# TinySparkShield.net
KiCad netlist of a schematic drawn in EAGLE
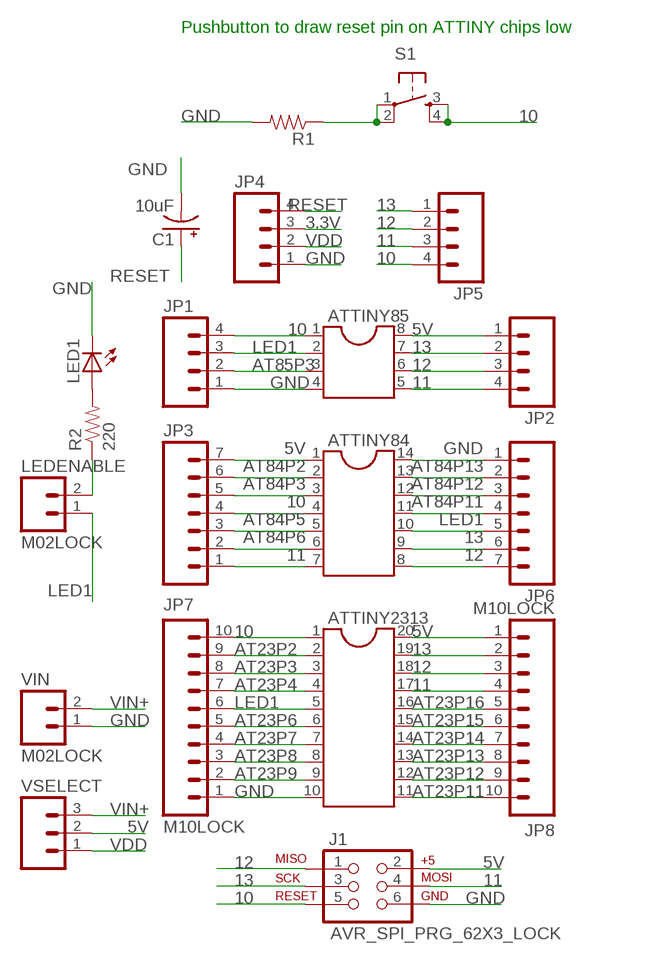
[diagram p0: schematic, sheet 1]

(export (version "E")
  (design (tool "Eeschema 10.0.6"))
  (components
    (comp (ref "ATTINY84")
      (value "DIL14")
      (footprint "eagle-import:DIL14")
      (libsource (lib "eagle-import") (part "DIL14"))
    )
    (comp (ref "ATTINY85")
      (value "DIL8")
      (footprint "eagle-import:DIL08")
      (libsource (lib "eagle-import") (part "DIL8"))
    )
    (comp (ref "ATTINY2313")
      (value "DIL20")
      (footprint "eagle-import:DIL20")
      (libsource (lib "eagle-import") (part "DIL20"))
    )
    (comp (ref "C1")
      (value "10uF")
      (footprint "eagle-import:CPOL-RADIAL-100UF-25V")
      (libsource (lib "eagle-import") (part "CAP_POLPTH1"))
    )
    (comp (ref "J1")
      (value "AVR_SPI_PRG_62X3_LOCK")
      (footprint "eagle-import:2X3_LOCK")
      (libsource (lib "eagle-import") (part "AVR_SPI_PRG_62X3_LOCK"))
    )
    (comp (ref "JP1")
      (value "M04LOCK")
      (footprint "eagle-import:1X04_LOCK")
      (libsource (lib "eagle-import") (part "M04LOCK"))
    )
    (comp (ref "JP2")
      (value "M04LOCK")
      (footprint "eagle-import:1X04_LOCK")
      (libsource (lib "eagle-import") (part "M04LOCK"))
    )
    (comp (ref "JP3")
      (value "M07LOCK")
      (footprint "eagle-import:1X07_LOCK")
      (libsource (lib "eagle-import") (part "M07LOCK"))
    )
    (comp (ref "JP4")
      (value "M04LOCK")
      (footprint "eagle-import:1X04_LOCK")
      (libsource (lib "eagle-import") (part "M04LOCK"))
    )
    (comp (ref "JP5")
      (value "M04LOCK")
      (footprint "eagle-import:1X04_LOCK")
      (libsource (lib "eagle-import") (part "M04LOCK"))
    )
    (comp (ref "JP6")
      (value "M07LOCK")
      (footprint "eagle-import:1X07_LOCK")
      (libsource (lib "eagle-import") (part "M07LOCK"))
    )
    (comp (ref "JP7")
      (value "M10LOCK")
      (footprint "eagle-import:1X10_LOCK")
      (libsource (lib "eagle-import") (part "M10LOCK"))
    )
    (comp (ref "JP8")
      (value "M10LOCK")
      (footprint "eagle-import:1X10_LOCK")
      (libsource (lib "eagle-import") (part "M10LOCK"))
    )
    (comp (ref "LED1")
      (value "LED3MM")
      (footprint "eagle-import:LED3MM")
      (libsource (lib "eagle-import") (part "LED3MM"))
    )
    (comp (ref "LEDENABLE")
      (value "M02LOCK")
      (footprint "eagle-import:1X02_LOCK")
      (libsource (lib "eagle-import") (part "M02LOCK"))
    )
    (comp (ref "R1")
      (value "RESISTORAXIAL-0.3")
      (footprint "eagle-import:AXIAL-0.3")
      (libsource (lib "eagle-import") (part "RESISTORAXIAL-0.3"))
    )
    (comp (ref "R2")
      (value "220")
      (footprint "eagle-import:AXIAL-0.3")
      (libsource (lib "eagle-import") (part "RESISTORAXIAL-0.3"))
    )
    (comp (ref "S1")
      (value "TAC_SWITCHPTH")
      (footprint "eagle-import:TACTILE-PTH")
      (libsource (lib "eagle-import") (part "TAC_SWITCHPTH"))
    )
    (comp (ref "VIN")
      (value "M02LOCK")
      (footprint "eagle-import:1X02_LOCK")
      (libsource (lib "eagle-import") (part "M02LOCK"))
    )
    (comp (ref "VSELECT")
      (value "M03LOCK")
      (footprint "eagle-import:1X03_LOCK")
      (libsource (lib "eagle-import") (part "M03LOCK"))
    )
  )
  (nets
    (net (code "1") (name "/3.3V") (class "Default")
      (node (ref "JP4") (pin "3") (pinfunction "3_3") (pintype "passive"))
    )
    (net (code "2") (name "/5V") (class "Default")
      (node (ref "ATTINY2313") (pin "20") (pinfunction "20_20") (pintype "passive"))
      (node (ref "ATTINY84") (pin "1") (pinfunction "1_1") (pintype "passive"))
      (node (ref "ATTINY85") (pin "8") (pinfunction "8_8") (pintype "passive"))
      (node (ref "J1") (pin "2") (pinfunction "2_2") (pintype "passive"))
      (node (ref "JP2") (pin "1") (pinfunction "1_1") (pintype "passive"))
      (node (ref "JP3") (pin "7") (pinfunction "7_7") (pintype "passive"))
      (node (ref "JP8") (pin "1") (pinfunction "1_1") (pintype "passive"))
      (node (ref "VSELECT") (pin "2") (pinfunction "2_2") (pintype "passive"))
    )
    (net (code "3") (name "/10") (class "Default")
      (node (ref "ATTINY2313") (pin "1") (pinfunction "1_1") (pintype "passive"))
      (node (ref "ATTINY84") (pin "4") (pinfunction "4_4") (pintype "passive"))
      (node (ref "ATTINY85") (pin "1") (pinfunction "1_1") (pintype "passive"))
      (node (ref "J1") (pin "5") (pinfunction "5_5") (pintype "passive"))
      (node (ref "JP1") (pin "4") (pinfunction "4_4") (pintype "passive"))
      (node (ref "JP3") (pin "4") (pinfunction "4_4") (pintype "passive"))
      (node (ref "JP5") (pin "4") (pinfunction "4_4") (pintype "passive"))
      (node (ref "JP7") (pin "10") (pinfunction "10_10") (pintype "passive"))
      (node (ref "S1") (pin "3") (pinfunction "3_3") (pintype "passive"))
      (node (ref "S1") (pin "4") (pinfunction "4_4") (pintype "passive"))
    )
    (net (code "4") (name "/11") (class "Default")
      (node (ref "ATTINY2313") (pin "17") (pinfunction "17_17") (pintype "passive"))
      (node (ref "ATTINY84") (pin "7") (pinfunction "7_7") (pintype "passive"))
      (node (ref "ATTINY85") (pin "5") (pinfunction "5_5") (pintype "passive"))
      (node (ref "J1") (pin "4") (pinfunction "4_4") (pintype "passive"))
      (node (ref "JP2") (pin "4") (pinfunction "4_4") (pintype "passive"))
      (node (ref "JP3") (pin "1") (pinfunction "1_1") (pintype "passive"))
      (node (ref "JP5") (pin "3") (pinfunction "3_3") (pintype "passive"))
      (node (ref "JP8") (pin "4") (pinfunction "4_4") (pintype "passive"))
    )
    (net (code "5") (name "/12") (class "Default")
      (node (ref "ATTINY2313") (pin "18") (pinfunction "18_18") (pintype "passive"))
      (node (ref "ATTINY84") (pin "8") (pinfunction "8_8") (pintype "passive"))
      (node (ref "ATTINY85") (pin "6") (pinfunction "6_6") (pintype "passive"))
      (node (ref "J1") (pin "1") (pinfunction "1_1") (pintype "passive"))
      (node (ref "JP2") (pin "3") (pinfunction "3_3") (pintype "passive"))
      (node (ref "JP5") (pin "2") (pinfunction "2_2") (pintype "passive"))
      (node (ref "JP6") (pin "7") (pinfunction "7_7") (pintype "passive"))
      (node (ref "JP8") (pin "3") (pinfunction "3_3") (pintype "passive"))
    )
    (net (code "6") (name "/13") (class "Default")
      (node (ref "ATTINY2313") (pin "19") (pinfunction "19_19") (pintype "passive"))
      (node (ref "ATTINY84") (pin "9") (pinfunction "9_9") (pintype "passive"))
      (node (ref "ATTINY85") (pin "7") (pinfunction "7_7") (pintype "passive"))
      (node (ref "J1") (pin "3") (pinfunction "3_3") (pintype "passive"))
      (node (ref "JP2") (pin "2") (pinfunction "2_2") (pintype "passive"))
      (node (ref "JP5") (pin "1") (pinfunction "1_1") (pintype "passive"))
      (node (ref "JP6") (pin "6") (pinfunction "6_6") (pintype "passive"))
      (node (ref "JP8") (pin "2") (pinfunction "2_2") (pintype "passive"))
    )
    (net (code "7") (name "/AT23P2") (class "Default")
      (node (ref "ATTINY2313") (pin "2") (pinfunction "2_2") (pintype "passive"))
      (node (ref "JP7") (pin "9") (pinfunction "9_9") (pintype "passive"))
    )
    (net (code "8") (name "/AT23P3") (class "Default")
      (node (ref "ATTINY2313") (pin "3") (pinfunction "3_3") (pintype "passive"))
      (node (ref "JP7") (pin "8") (pinfunction "8_8") (pintype "passive"))
    )
    (net (code "9") (name "/AT23P4") (class "Default")
      (node (ref "ATTINY2313") (pin "4") (pinfunction "4_4") (pintype "passive"))
      (node (ref "JP7") (pin "7") (pinfunction "7_7") (pintype "passive"))
    )
    (net (code "10") (name "/AT23P6") (class "Default")
      (node (ref "ATTINY2313") (pin "6") (pinfunction "6_6") (pintype "passive"))
      (node (ref "JP7") (pin "5") (pinfunction "5_5") (pintype "passive"))
    )
    (net (code "11") (name "/AT23P7") (class "Default")
      (node (ref "ATTINY2313") (pin "7") (pinfunction "7_7") (pintype "passive"))
      (node (ref "JP7") (pin "4") (pinfunction "4_4") (pintype "passive"))
    )
    (net (code "12") (name "/AT23P8") (class "Default")
      (node (ref "ATTINY2313") (pin "8") (pinfunction "8_8") (pintype "passive"))
      (node (ref "JP7") (pin "3") (pinfunction "3_3") (pintype "passive"))
    )
    (net (code "13") (name "/AT23P9") (class "Default")
      (node (ref "ATTINY2313") (pin "9") (pinfunction "9_9") (pintype "passive"))
      (node (ref "JP7") (pin "2") (pinfunction "2_2") (pintype "passive"))
    )
    (net (code "14") (name "/AT23P11") (class "Default")
      (node (ref "ATTINY2313") (pin "11") (pinfunction "11_11") (pintype "passive"))
      (node (ref "JP8") (pin "10") (pinfunction "10_10") (pintype "passive"))
    )
    (net (code "15") (name "/AT23P12") (class "Default")
      (node (ref "ATTINY2313") (pin "12") (pinfunction "12_12") (pintype "passive"))
      (node (ref "JP8") (pin "9") (pinfunction "9_9") (pintype "passive"))
    )
    (net (code "16") (name "/AT23P13") (class "Default")
      (node (ref "ATTINY2313") (pin "13") (pinfunction "13_13") (pintype "passive"))
      (node (ref "JP8") (pin "8") (pinfunction "8_8") (pintype "passive"))
    )
    (net (code "17") (name "/AT23P14") (class "Default")
      (node (ref "ATTINY2313") (pin "14") (pinfunction "14_14") (pintype "passive"))
      (node (ref "JP8") (pin "7") (pinfunction "7_7") (pintype "passive"))
    )
    (net (code "18") (name "/AT23P15") (class "Default")
      (node (ref "ATTINY2313") (pin "15") (pinfunction "15_15") (pintype "passive"))
      (node (ref "JP8") (pin "6") (pinfunction "6_6") (pintype "passive"))
    )
    (net (code "19") (name "/AT23P16") (class "Default")
      (node (ref "ATTINY2313") (pin "16") (pinfunction "16_16") (pintype "passive"))
      (node (ref "JP8") (pin "5") (pinfunction "5_5") (pintype "passive"))
    )
    (net (code "20") (name "/AT84P2") (class "Default")
      (node (ref "ATTINY84") (pin "2") (pinfunction "2_2") (pintype "passive"))
      (node (ref "JP3") (pin "6") (pinfunction "6_6") (pintype "passive"))
    )
    (net (code "21") (name "/AT84P3") (class "Default")
      (node (ref "ATTINY84") (pin "3") (pinfunction "3_3") (pintype "passive"))
      (node (ref "JP3") (pin "5") (pinfunction "5_5") (pintype "passive"))
    )
    (net (code "22") (name "/AT84P5") (class "Default")
      (node (ref "ATTINY84") (pin "5") (pinfunction "5_5") (pintype "passive"))
      (node (ref "JP3") (pin "3") (pinfunction "3_3") (pintype "passive"))
    )
    (net (code "23") (name "/AT84P6") (class "Default")
      (node (ref "ATTINY84") (pin "6") (pinfunction "6_6") (pintype "passive"))
      (node (ref "JP3") (pin "2") (pinfunction "2_2") (pintype "passive"))
    )
    (net (code "24") (name "/AT84P11") (class "Default")
      (node (ref "ATTINY84") (pin "11") (pinfunction "11_11") (pintype "passive"))
      (node (ref "JP6") (pin "4") (pinfunction "4_4") (pintype "passive"))
    )
    (net (code "25") (name "/AT84P12") (class "Default")
      (node (ref "ATTINY84") (pin "12") (pinfunction "12_12") (pintype "passive"))
      (node (ref "JP6") (pin "3") (pinfunction "3_3") (pintype "passive"))
    )
    (net (code "26") (name "/AT84P13") (class "Default")
      (node (ref "ATTINY84") (pin "13") (pinfunction "13_13") (pintype "passive"))
      (node (ref "JP6") (pin "2") (pinfunction "2_2") (pintype "passive"))
    )
    (net (code "27") (name "/AT85P3") (class "Default")
      (node (ref "ATTINY85") (pin "3") (pinfunction "3_3") (pintype "passive"))
      (node (ref "JP1") (pin "2") (pinfunction "2_2") (pintype "passive"))
    )
    (net (code "28") (name "/GND") (class "Default")
      (node (ref "ATTINY2313") (pin "10") (pinfunction "10_10") (pintype "passive"))
      (node (ref "ATTINY84") (pin "14") (pinfunction "14_14") (pintype "passive"))
      (node (ref "ATTINY85") (pin "4") (pinfunction "4_4") (pintype "passive"))
      (node (ref "C1") (pin "2") (pinfunction "-_2") (pintype "passive"))
      (node (ref "J1") (pin "6") (pinfunction "6_6") (pintype "passive"))
      (node (ref "JP1") (pin "1") (pinfunction "1_1") (pintype "passive"))
      (node (ref "JP4") (pin "1") (pinfunction "1_1") (pintype "passive"))
      (node (ref "JP6") (pin "1") (pinfunction "1_1") (pintype "passive"))
      (node (ref "JP7") (pin "1") (pinfunction "1_1") (pintype "passive"))
      (node (ref "LED1") (pin "K") (pinfunction "C_K") (pintype "passive"))
      (node (ref "R1") (pin "P$2") (pinfunction "2_P$2") (pintype "passive"))
      (node (ref "VIN") (pin "1") (pinfunction "1_1") (pintype "passive"))
    )
    (net (code "29") (name "/LED1") (class "Default")
      (node (ref "ATTINY2313") (pin "5") (pinfunction "5_5") (pintype "passive"))
      (node (ref "ATTINY84") (pin "10") (pinfunction "10_10") (pintype "passive"))
      (node (ref "ATTINY85") (pin "2") (pinfunction "2_2") (pintype "passive"))
      (node (ref "JP1") (pin "3") (pinfunction "3_3") (pintype "passive"))
      (node (ref "JP6") (pin "5") (pinfunction "5_5") (pintype "passive"))
      (node (ref "JP7") (pin "6") (pinfunction "6_6") (pintype "passive"))
      (node (ref "LEDENABLE") (pin "1") (pinfunction "1_1") (pintype "passive"))
    )
    (net (code "30") (name "/RESET") (class "Default")
      (node (ref "C1") (pin "1") (pinfunction "+_1") (pintype "passive"))
      (node (ref "JP4") (pin "4") (pinfunction "4_4") (pintype "passive"))
    )
    (net (code "31") (name "/VDD") (class "Default")
      (node (ref "JP4") (pin "2") (pinfunction "2_2") (pintype "passive"))
      (node (ref "VSELECT") (pin "1") (pinfunction "1_1") (pintype "passive"))
    )
    (net (code "32") (name "/VIN+") (class "Default")
      (node (ref "VIN") (pin "2") (pinfunction "2_2") (pintype "passive"))
      (node (ref "VSELECT") (pin "3") (pinfunction "3_3") (pintype "passive"))
    )
    (net (code "33") (name "Net-(R1-1)") (class "Default")
      (node (ref "R1") (pin "P$1") (pinfunction "1_P$1") (pintype "passive"))
      (node (ref "S1") (pin "1") (pinfunction "1_1") (pintype "passive"))
      (node (ref "S1") (pin "2") (pinfunction "2_2") (pintype "passive"))
    )
    (net (code "34") (name "Net-(R2-1)") (class "Default")
      (node (ref "LEDENABLE") (pin "2") (pinfunction "2_2") (pintype "passive"))
      (node (ref "R2") (pin "P$1") (pinfunction "1_P$1") (pintype "passive"))
    )
    (net (code "35") (name "Net-(R2-2)") (class "Default")
      (node (ref "LED1") (pin "A") (pinfunction "A_A") (pintype "passive"))
      (node (ref "R2") (pin "P$2") (pinfunction "2_P$2") (pintype "passive"))
    )
  )
)
